# Blueboard_Pro_v1_1.net
KiCad netlist of a schematic drawn in EAGLE
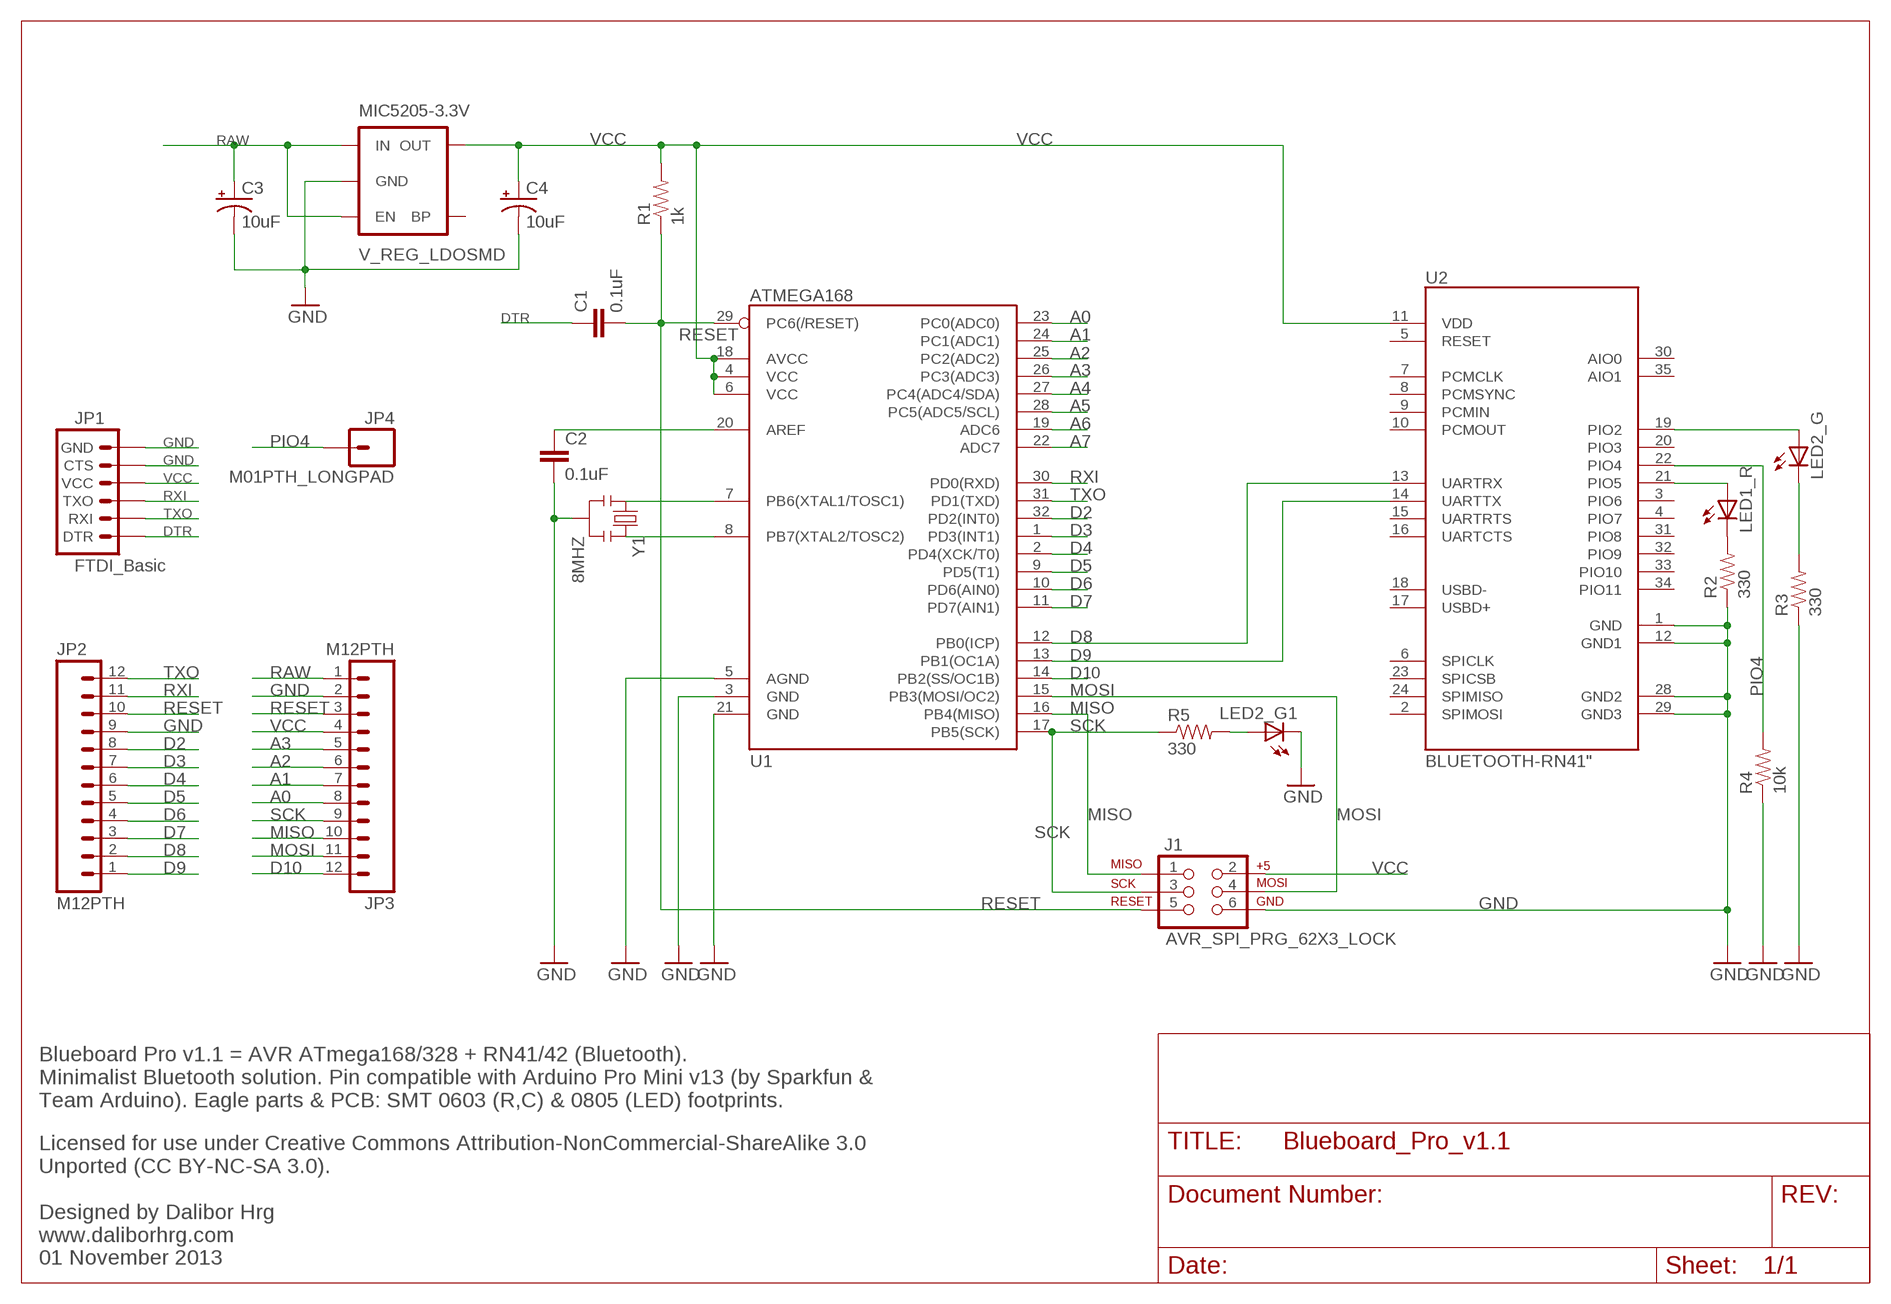
[diagram p0: schematic, sheet 1]

(export (version "E")
  (design (tool "Eeschema 10.0.6"))
  (components
    (comp (ref "C1")
      (value "0.1uF")
      (footprint "eagle-import:0603-CAP")
      (libsource (lib "eagle-import") (part "SparkFun-Passives_CAP0603-CAP"))
    )
    (comp (ref "C2")
      (value "0.1uF")
      (footprint "eagle-import:0603-CAP")
      (libsource (lib "eagle-import") (part "CAP0603-CAP"))
    )
    (comp (ref "C3")
      (value "10uF")
      (footprint "eagle-import:EIA3216")
      (libsource (lib "eagle-import") (part "10UF-16V-10%(TANT)"))
    )
    (comp (ref "C4")
      (value "10uF")
      (footprint "eagle-import:EIA3216")
      (libsource (lib "eagle-import") (part "10UF-16V-10%(TANT)"))
    )
    (comp (ref "J1")
      (value "AVR_SPI_PRG_62X3_LOCK")
      (footprint "eagle-import:2X3_LOCK")
      (libsource (lib "eagle-import") (part "AVR_SPI_PRG_62X3_LOCK"))
    )
    (comp (ref "JP1")
      (value "FTDI_Basic")
      (footprint "eagle-import:1X06")
      (libsource (lib "eagle-import") (part "ARDUINO_SERIAL_PROGRAMPTH"))
    )
    (comp (ref "JP2")
      (value "M12PTH")
      (footprint "eagle-import:1X12")
      (libsource (lib "eagle-import") (part "M12PTH"))
    )
    (comp (ref "JP3")
      (value "M12PTH")
      (footprint "eagle-import:1X12")
      (libsource (lib "eagle-import") (part "M12PTH"))
    )
    (comp (ref "JP4")
      (value "M01PTH_LONGPAD")
      (footprint "eagle-import:1X01_LONGPAD")
      (libsource (lib "eagle-import") (part "M01PTH_LONGPAD"))
    )
    (comp (ref "LED1_R")
      (value "LEDCHIP-LED0805")
      (footprint "eagle-import:CHIP-LED0805")
      (libsource (lib "eagle-import") (part "LEDCHIP-LED0805"))
    )
    (comp (ref "LED2_G")
      (value "LEDCHIP-LED0805")
      (footprint "eagle-import:CHIP-LED0805")
      (libsource (lib "eagle-import") (part "LEDCHIP-LED0805"))
    )
    (comp (ref "LED2_G1")
      (value "LEDCHIP-LED0805")
      (footprint "eagle-import:CHIP-LED0805")
      (libsource (lib "eagle-import") (part "LEDCHIP-LED0805"))
    )
    (comp (ref "MIC5205-3.3V")
      (value "V_REG_LDOSMD")
      (footprint "eagle-import:SOT23-5")
      (libsource (lib "eagle-import") (part "V_REG_LDOSMD"))
    )
    (comp (ref "R1")
      (value "1k")
      (footprint "eagle-import:0603-RES")
      (libsource (lib "eagle-import") (part "1K-1%"))
    )
    (comp (ref "R2")
      (value "330")
      (footprint "eagle-import:0603-RES")
      (libsource (lib "eagle-import") (part "RESISTOR0603-RES"))
    )
    (comp (ref "R3")
      (value "330")
      (footprint "eagle-import:0603-RES")
      (libsource (lib "eagle-import") (part "RESISTOR0603-RES"))
    )
    (comp (ref "R4")
      (value "10k")
      (footprint "eagle-import:0603-RES")
      (libsource (lib "eagle-import") (part "RESISTOR0603"))
    )
    (comp (ref "R5")
      (value "330")
      (footprint "eagle-import:0603-RES")
      (libsource (lib "eagle-import") (part "RESISTOR0603-RES"))
    )
    (comp (ref "U1")
      (value "ATMEGA168")
      (footprint "eagle-import:TQFP32-08")
      (libsource (lib "eagle-import") (part "ATMEGA168"))
    )
    (comp (ref "U2")
      (value "BLUETOOTH-RN41\"")
      (footprint "eagle-import:RN41")
      (libsource (lib "eagle-import") (part "BLUETOOTH-RN41{dblquote}"))
    )
    (comp (ref "Y1")
      (value "8MHZ")
      (footprint "eagle-import:RESONATOR-SMD")
      (libsource (lib "eagle-import") (part "RESONATOR8MHZ"))
    )
  )
  (nets
    (net (code "1") (name "/A0") (class "Default")
      (node (ref "JP3") (pin "8") (pinfunction "8_8") (pintype "passive"))
      (node (ref "U1") (pin "23") (pinfunction "PC0(ADC0)_23") (pintype "bidirectional"))
    )
    (net (code "2") (name "/A1") (class "Default")
      (node (ref "JP3") (pin "7") (pinfunction "7_7") (pintype "passive"))
      (node (ref "U1") (pin "24") (pinfunction "PC1(ADC1)_24") (pintype "bidirectional"))
    )
    (net (code "3") (name "/A2") (class "Default")
      (node (ref "JP3") (pin "6") (pinfunction "6_6") (pintype "passive"))
      (node (ref "U1") (pin "25") (pinfunction "PC2(ADC2)_25") (pintype "bidirectional"))
    )
    (net (code "4") (name "/A3") (class "Default")
      (node (ref "JP3") (pin "5") (pinfunction "5_5") (pintype "passive"))
      (node (ref "U1") (pin "26") (pinfunction "PC3(ADC3)_26") (pintype "bidirectional"))
    )
    (net (code "5") (name "/A4") (class "Default")
      (node (ref "U1") (pin "27") (pinfunction "PC4(ADC4/SDA)_27") (pintype "bidirectional"))
    )
    (net (code "6") (name "/A5") (class "Default")
      (node (ref "U1") (pin "28") (pinfunction "PC5(ADC5/SCL)_28") (pintype "bidirectional"))
    )
    (net (code "7") (name "/A6") (class "Default")
      (node (ref "U1") (pin "19") (pinfunction "ADC6_19") (pintype "bidirectional"))
    )
    (net (code "8") (name "/A7") (class "Default")
      (node (ref "U1") (pin "22") (pinfunction "ADC7_22") (pintype "bidirectional"))
    )
    (net (code "9") (name "/D2") (class "Default")
      (node (ref "JP2") (pin "8") (pinfunction "8_8") (pintype "passive"))
      (node (ref "U1") (pin "32") (pinfunction "PD2(INT0)_32") (pintype "bidirectional"))
    )
    (net (code "10") (name "/D3") (class "Default")
      (node (ref "JP2") (pin "7") (pinfunction "7_7") (pintype "passive"))
      (node (ref "U1") (pin "1") (pinfunction "PD3(INT1)_1") (pintype "bidirectional"))
    )
    (net (code "11") (name "/D4") (class "Default")
      (node (ref "JP2") (pin "6") (pinfunction "6_6") (pintype "passive"))
      (node (ref "U1") (pin "2") (pinfunction "PD4(XCK/T0)_2") (pintype "bidirectional"))
    )
    (net (code "12") (name "/D5") (class "Default")
      (node (ref "JP2") (pin "5") (pinfunction "5_5") (pintype "passive"))
      (node (ref "U1") (pin "9") (pinfunction "PD5(T1)_9") (pintype "bidirectional"))
    )
    (net (code "13") (name "/D6") (class "Default")
      (node (ref "JP2") (pin "4") (pinfunction "4_4") (pintype "passive"))
      (node (ref "U1") (pin "10") (pinfunction "PD6(AIN0)_10") (pintype "bidirectional"))
    )
    (net (code "14") (name "/D7") (class "Default")
      (node (ref "JP2") (pin "3") (pinfunction "3_3") (pintype "passive"))
      (node (ref "U1") (pin "11") (pinfunction "PD7(AIN1)_11") (pintype "bidirectional"))
    )
    (net (code "15") (name "/D8") (class "Default")
      (node (ref "JP2") (pin "2") (pinfunction "2_2") (pintype "passive"))
      (node (ref "U1") (pin "12") (pinfunction "PB0(ICP)_12") (pintype "bidirectional"))
      (node (ref "U2") (pin "13") (pinfunction "UARTRX_13") (pintype "bidirectional"))
    )
    (net (code "16") (name "/D9") (class "Default")
      (node (ref "JP2") (pin "1") (pinfunction "1_1") (pintype "passive"))
      (node (ref "U1") (pin "13") (pinfunction "PB1(OC1A)_13") (pintype "bidirectional"))
      (node (ref "U2") (pin "14") (pinfunction "UARTTX_14") (pintype "bidirectional"))
    )
    (net (code "17") (name "/D10") (class "Default")
      (node (ref "JP3") (pin "12") (pinfunction "12_12") (pintype "passive"))
      (node (ref "U1") (pin "14") (pinfunction "PB2(SS/OC1B)_14") (pintype "bidirectional"))
    )
    (net (code "18") (name "/DTR") (class "Default")
      (node (ref "C1") (pin "1") (pinfunction "1_1") (pintype "passive"))
      (node (ref "JP1") (pin "1") (pinfunction "DTR_1") (pintype "passive"))
    )
    (net (code "19") (name "/MISO") (class "Default")
      (node (ref "J1") (pin "1") (pinfunction "1_1") (pintype "passive"))
      (node (ref "JP3") (pin "10") (pinfunction "10_10") (pintype "passive"))
      (node (ref "U1") (pin "16") (pinfunction "PB4(MISO)_16") (pintype "bidirectional"))
    )
    (net (code "20") (name "/MOSI") (class "Default")
      (node (ref "J1") (pin "4") (pinfunction "4_4") (pintype "passive"))
      (node (ref "JP3") (pin "11") (pinfunction "11_11") (pintype "passive"))
      (node (ref "U1") (pin "15") (pinfunction "PB3(MOSI/OC2)_15") (pintype "bidirectional"))
    )
    (net (code "21") (name "/PIO4") (class "Default")
      (node (ref "JP4") (pin "1") (pinfunction "1_1") (pintype "passive"))
      (node (ref "R4") (pin "2") (pinfunction "2_2") (pintype "passive"))
      (node (ref "U2") (pin "22") (pinfunction "PIO4_22") (pintype "bidirectional"))
    )
    (net (code "22") (name "/RAW") (class "Default")
      (node (ref "C3") (pin "A") (pinfunction "+_A") (pintype "passive"))
      (node (ref "JP3") (pin "1") (pinfunction "1_1") (pintype "passive"))
      (node (ref "MIC5205-3.3V") (pin "1") (pinfunction "IN_1") (pintype "input"))
      (node (ref "MIC5205-3.3V") (pin "3") (pinfunction "EN_3") (pintype "input"))
    )
    (net (code "23") (name "/RESET") (class "Default")
      (node (ref "C1") (pin "2") (pinfunction "2_2") (pintype "passive"))
      (node (ref "J1") (pin "5") (pinfunction "5_5") (pintype "passive"))
      (node (ref "JP2") (pin "10") (pinfunction "10_10") (pintype "passive"))
      (node (ref "JP3") (pin "3") (pinfunction "3_3") (pintype "passive"))
      (node (ref "R1") (pin "1") (pinfunction "1_1") (pintype "passive"))
      (node (ref "U1") (pin "29") (pinfunction "PC6(/RESET)_29") (pintype "bidirectional"))
    )
    (net (code "24") (name "/RXI") (class "Default")
      (node (ref "JP1") (pin "3") (pinfunction "TXO_3") (pintype "passive"))
      (node (ref "JP2") (pin "11") (pinfunction "11_11") (pintype "passive"))
      (node (ref "U1") (pin "30") (pinfunction "PD0(RXD)_30") (pintype "bidirectional"))
    )
    (net (code "25") (name "/SCK") (class "Default")
      (node (ref "J1") (pin "3") (pinfunction "3_3") (pintype "passive"))
      (node (ref "JP3") (pin "9") (pinfunction "9_9") (pintype "passive"))
      (node (ref "R5") (pin "1") (pinfunction "1_1") (pintype "passive"))
      (node (ref "U1") (pin "17") (pinfunction "PB5(SCK)_17") (pintype "bidirectional"))
    )
    (net (code "26") (name "/TXO") (class "Default")
      (node (ref "JP1") (pin "2") (pinfunction "RXI_2") (pintype "passive"))
      (node (ref "JP2") (pin "12") (pinfunction "12_12") (pintype "passive"))
      (node (ref "U1") (pin "31") (pinfunction "PD1(TXD)_31") (pintype "bidirectional"))
    )
    (net (code "27") (name "/VCC") (class "Default")
      (node (ref "C4") (pin "A") (pinfunction "+_A") (pintype "passive"))
      (node (ref "J1") (pin "2") (pinfunction "2_2") (pintype "passive"))
      (node (ref "JP1") (pin "4") (pinfunction "VCC_4") (pintype "passive"))
      (node (ref "JP3") (pin "4") (pinfunction "4_4") (pintype "passive"))
      (node (ref "MIC5205-3.3V") (pin "5") (pinfunction "OUT_5") (pintype "passive"))
      (node (ref "R1") (pin "2") (pinfunction "2_2") (pintype "passive"))
      (node (ref "U1") (pin "18") (pinfunction "AVCC_18") (pintype "bidirectional"))
      (node (ref "U1") (pin "4") (pinfunction "VCC_4") (pintype "bidirectional"))
      (node (ref "U1") (pin "6") (pinfunction "VCC_6") (pintype "bidirectional"))
      (node (ref "U2") (pin "11") (pinfunction "VDD_11") (pintype "bidirectional"))
    )
    (net (code "28") (name "GND") (class "Default")
      (node (ref "C2") (pin "2") (pinfunction "2_2") (pintype "passive"))
      (node (ref "C3") (pin "C") (pinfunction "-_C") (pintype "passive"))
      (node (ref "C4") (pin "C") (pinfunction "-_C") (pintype "passive"))
      (node (ref "J1") (pin "6") (pinfunction "6_6") (pintype "passive"))
      (node (ref "JP1") (pin "5") (pinfunction "CTS_5") (pintype "passive"))
      (node (ref "JP1") (pin "6") (pinfunction "GND_6") (pintype "passive"))
      (node (ref "JP2") (pin "9") (pinfunction "9_9") (pintype "passive"))
      (node (ref "JP3") (pin "2") (pinfunction "2_2") (pintype "passive"))
      (node (ref "LED2_G1") (pin "C") (pinfunction "C_C") (pintype "passive"))
      (node (ref "MIC5205-3.3V") (pin "2") (pinfunction "GND_2") (pintype "input"))
      (node (ref "R2") (pin "1") (pinfunction "1_1") (pintype "passive"))
      (node (ref "R3") (pin "1") (pinfunction "1_1") (pintype "passive"))
      (node (ref "R4") (pin "1") (pinfunction "1_1") (pintype "passive"))
      (node (ref "U1") (pin "21") (pinfunction "GND_21") (pintype "bidirectional"))
      (node (ref "U1") (pin "3") (pinfunction "GND_3") (pintype "bidirectional"))
      (node (ref "U1") (pin "5") (pinfunction "AGND_5") (pintype "bidirectional"))
      (node (ref "U2") (pin "1") (pinfunction "GND_1") (pintype "bidirectional"))
      (node (ref "U2") (pin "12") (pinfunction "GND1_12") (pintype "bidirectional"))
      (node (ref "U2") (pin "28") (pinfunction "GND2_28") (pintype "bidirectional"))
      (node (ref "U2") (pin "29") (pinfunction "GND3_29") (pintype "bidirectional"))
      (node (ref "Y1") (pin "2") (pinfunction "2_2") (pintype "passive"))
    )
    (net (code "29") (name "Net-(LED1_R-PadC)") (class "Default")
      (node (ref "LED1_R") (pin "C") (pinfunction "C_C") (pintype "passive"))
      (node (ref "R2") (pin "2") (pinfunction "2_2") (pintype "passive"))
    )
    (net (code "30") (name "Net-(LED2_G-PadC)") (class "Default")
      (node (ref "LED2_G") (pin "C") (pinfunction "C_C") (pintype "passive"))
      (node (ref "R3") (pin "2") (pinfunction "2_2") (pintype "passive"))
    )
    (net (code "31") (name "Net-(LED2_G1-PadA)") (class "Default")
      (node (ref "LED2_G1") (pin "A") (pinfunction "A_A") (pintype "passive"))
      (node (ref "R5") (pin "2") (pinfunction "2_2") (pintype "passive"))
    )
    (net (code "32") (name "Net-(U1-AREF)") (class "Default")
      (node (ref "C2") (pin "1") (pinfunction "1_1") (pintype "passive"))
      (node (ref "U1") (pin "20") (pinfunction "AREF_20") (pintype "bidirectional"))
    )
    (net (code "33") (name "Net-(U1-PB6(XTAL1{slash}TOSC1))") (class "Default")
      (node (ref "U1") (pin "7") (pinfunction "PB6(XTAL1/TOSC1)_7") (pintype "bidirectional"))
      (node (ref "Y1") (pin "1") (pinfunction "1_1") (pintype "passive"))
    )
    (net (code "34") (name "Net-(U1-PB7(XTAL2{slash}TOSC2))") (class "Default")
      (node (ref "U1") (pin "8") (pinfunction "PB7(XTAL2/TOSC2)_8") (pintype "bidirectional"))
      (node (ref "Y1") (pin "3") (pinfunction "3_3") (pintype "passive"))
    )
    (net (code "35") (name "Net-(U2-PIO2)") (class "Default")
      (node (ref "LED2_G") (pin "A") (pinfunction "A_A") (pintype "passive"))
      (node (ref "U2") (pin "19") (pinfunction "PIO2_19") (pintype "bidirectional"))
    )
    (net (code "36") (name "Net-(U2-PIO5)") (class "Default")
      (node (ref "LED1_R") (pin "A") (pinfunction "A_A") (pintype "passive"))
      (node (ref "U2") (pin "21") (pinfunction "PIO5_21") (pintype "bidirectional"))
    )
    (net (code "37") (name "unconnected-(MIC5205-3.3V-BP-Pad4)") (class "Default")
      (node (ref "MIC5205-3.3V") (pin "4") (pinfunction "BP_4") (pintype "input"))
    )
    (net (code "38") (name "unconnected-(U2-AIO0-Pad30)") (class "Default")
      (node (ref "U2") (pin "30") (pinfunction "AIO0_30") (pintype "bidirectional"))
    )
    (net (code "39") (name "unconnected-(U2-AIO1-Pad35)") (class "Default")
      (node (ref "U2") (pin "35") (pinfunction "AIO1_35") (pintype "bidirectional"))
    )
    (net (code "40") (name "unconnected-(U2-PCMCLK-Pad7)") (class "Default")
      (node (ref "U2") (pin "7") (pinfunction "PCMCLK_7") (pintype "bidirectional"))
    )
    (net (code "41") (name "unconnected-(U2-PCMIN-Pad9)") (class "Default")
      (node (ref "U2") (pin "9") (pinfunction "PCMIN_9") (pintype "bidirectional"))
    )
    (net (code "42") (name "unconnected-(U2-PCMOUT-Pad10)") (class "Default")
      (node (ref "U2") (pin "10") (pinfunction "PCMOUT_10") (pintype "bidirectional"))
    )
    (net (code "43") (name "unconnected-(U2-PCMSYNC-Pad8)") (class "Default")
      (node (ref "U2") (pin "8") (pinfunction "PCMSYNC_8") (pintype "bidirectional"))
    )
    (net (code "44") (name "unconnected-(U2-PIO3-Pad20)") (class "Default")
      (node (ref "U2") (pin "20") (pinfunction "PIO3_20") (pintype "bidirectional"))
    )
    (net (code "45") (name "unconnected-(U2-PIO6-Pad3)") (class "Default")
      (node (ref "U2") (pin "3") (pinfunction "PIO6_3") (pintype "bidirectional"))
    )
    (net (code "46") (name "unconnected-(U2-PIO7-Pad4)") (class "Default")
      (node (ref "U2") (pin "4") (pinfunction "PIO7_4") (pintype "bidirectional"))
    )
    (net (code "47") (name "unconnected-(U2-PIO8-Pad31)") (class "Default")
      (node (ref "U2") (pin "31") (pinfunction "PIO8_31") (pintype "bidirectional"))
    )
    (net (code "48") (name "unconnected-(U2-PIO9-Pad32)") (class "Default")
      (node (ref "U2") (pin "32") (pinfunction "PIO9_32") (pintype "bidirectional"))
    )
    (net (code "49") (name "unconnected-(U2-PIO10-Pad33)") (class "Default")
      (node (ref "U2") (pin "33") (pinfunction "PIO10_33") (pintype "bidirectional"))
    )
    (net (code "50") (name "unconnected-(U2-PIO11-Pad34)") (class "Default")
      (node (ref "U2") (pin "34") (pinfunction "PIO11_34") (pintype "bidirectional"))
    )
    (net (code "51") (name "unconnected-(U2-RESET-Pad5)") (class "Default")
      (node (ref "U2") (pin "5") (pinfunction "RESET_5") (pintype "bidirectional"))
    )
    (net (code "52") (name "unconnected-(U2-SPICLK-Pad6)") (class "Default")
      (node (ref "U2") (pin "6") (pinfunction "SPICLK_6") (pintype "bidirectional"))
    )
    (net (code "53") (name "unconnected-(U2-SPICSB-Pad23)") (class "Default")
      (node (ref "U2") (pin "23") (pinfunction "SPICSB_23") (pintype "bidirectional"))
    )
    (net (code "54") (name "unconnected-(U2-SPIMISO-Pad24)") (class "Default")
      (node (ref "U2") (pin "24") (pinfunction "SPIMISO_24") (pintype "bidirectional"))
    )
    (net (code "55") (name "unconnected-(U2-SPIMOSI-Pad2)") (class "Default")
      (node (ref "U2") (pin "2") (pinfunction "SPIMOSI_2") (pintype "bidirectional"))
    )
    (net (code "56") (name "unconnected-(U2-UARTCTS-Pad16)") (class "Default")
      (node (ref "U2") (pin "16") (pinfunction "UARTCTS_16") (pintype "bidirectional"))
    )
    (net (code "57") (name "unconnected-(U2-UARTRTS-Pad15)") (class "Default")
      (node (ref "U2") (pin "15") (pinfunction "UARTRTS_15") (pintype "bidirectional"))
    )
    (net (code "58") (name "unconnected-(U2-USBD+-Pad17)") (class "Default")
      (node (ref "U2") (pin "17") (pinfunction "USBD+_17") (pintype "bidirectional"))
    )
    (net (code "59") (name "unconnected-(U2-USBD--Pad18)") (class "Default")
      (node (ref "U2") (pin "18") (pinfunction "USBD-_18") (pintype "bidirectional"))
    )
  )
)
